# PX4FMUv2_4_6_9.net
KiCad netlist of a schematic drawn in Altium Designer
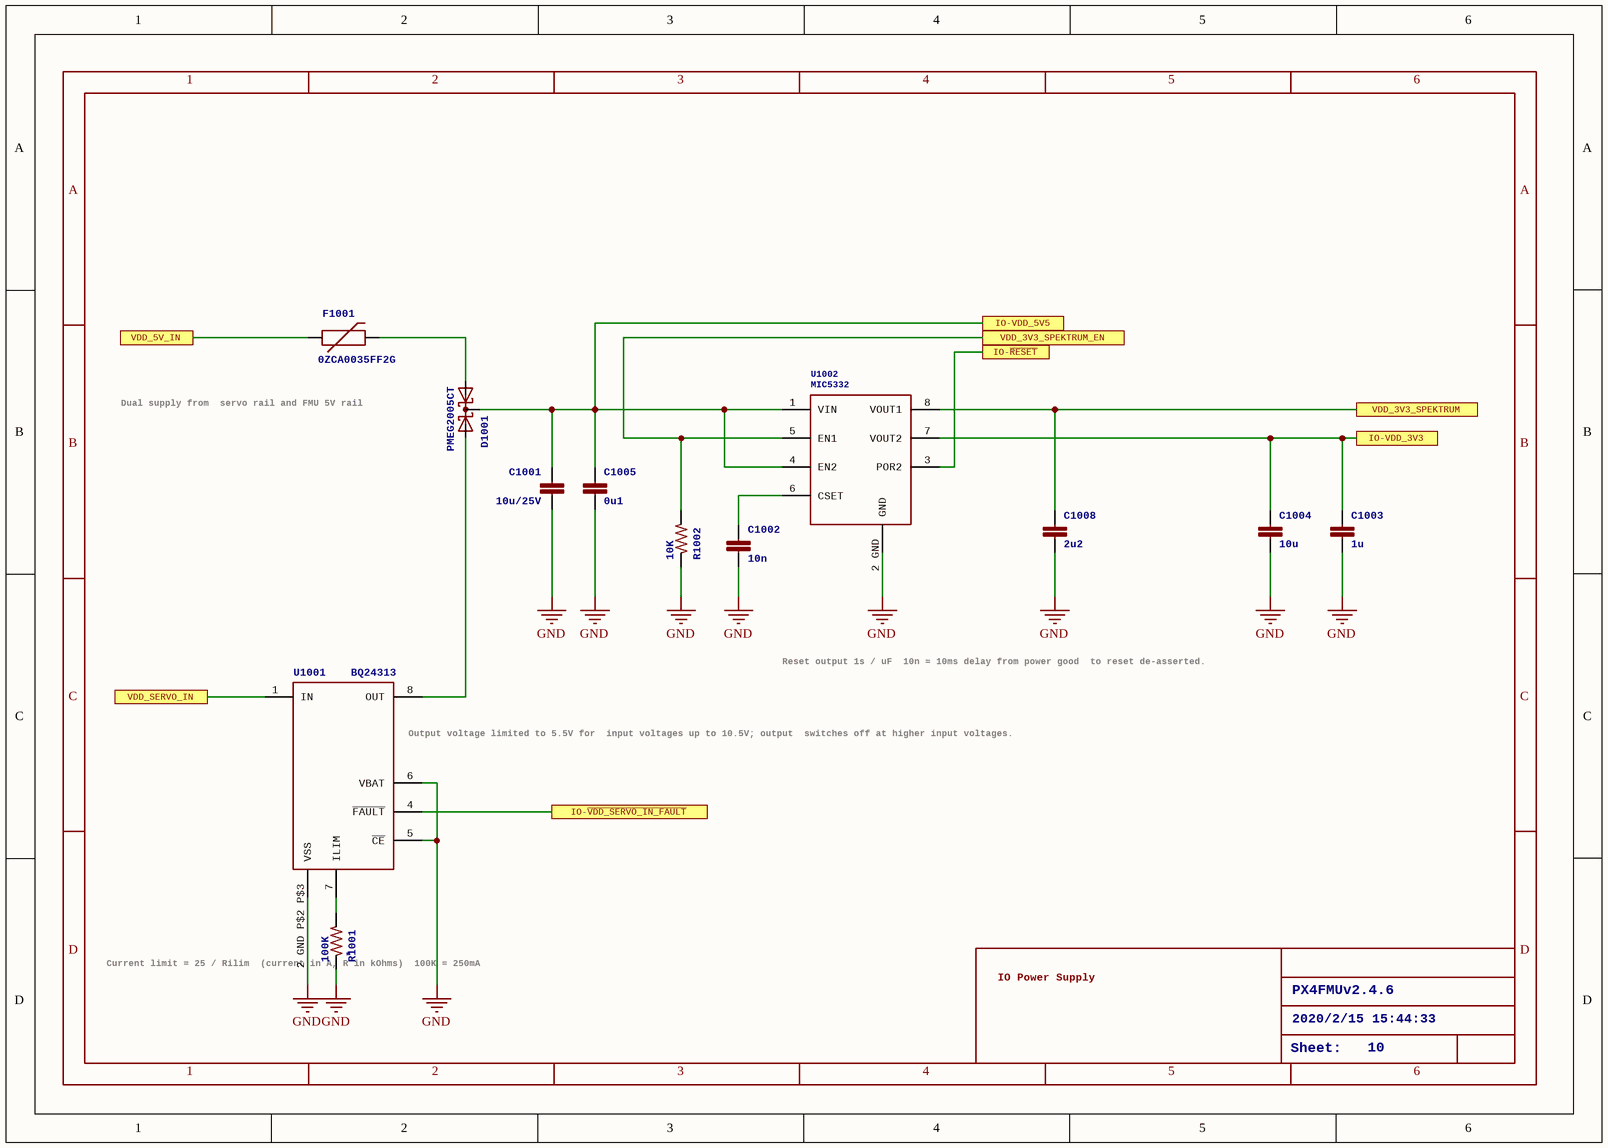
[diagram p0: PX4FMUv2.4.6_9.SchDoc]

(export (version "E")
  (design (tool "Eeschema 10.0.6"))
  (components
    (comp (ref "C1001")
      (value "10u/25V")
      (footprint "0805-CAP")
      (description "CapacitorStandard 0603 ceramic capacitor, and 0.1\" leaded capacitor.")
      (fields (field (name "PARTNO") "CL21A106KAYNNNE"))
      (libsource (lib "pixhawk2") (part "CAP0805"))
    )
    (comp (ref "C1002")
      (value "10n")
      (footprint "0402-CAP")
      (description "CapacitorStandard 0603 ceramic capacitor, and 0.1\" leaded capacitor.")
      (fields (field (name "PARTNO") "CC0402KRX7R7BB103"))
      (libsource (lib "pixhawk2") (part "CAP0402"))
    )
    (comp (ref "C1003")
      (value "1u")
      (footprint "0603-CAP")
      (description "CapacitorStandard 0603 ceramic capacitor, and 0.1\" leaded capacitor.")
      (fields (field (name "PARTNO") "CC0603ZRY5V7BB105"))
      (libsource (lib "pixhawk2") (part "CAP0603"))
    )
    (comp (ref "C1004")
      (value "10u")
      (footprint "0603-CAP")
      (description "CapacitorStandard 0603 ceramic capacitor, and 0.1\" leaded capacitor.")
      (fields (field (name "PARTNO") "C1608X5R1A106K080AC"))
      (libsource (lib "pixhawk2") (part "CAP0603"))
    )
    (comp (ref "C1005")
      (value "0u1")
      (footprint "0402-CAP")
      (description "CapacitorStandard 0603 ceramic capacitor, and 0.1\" leaded capacitor.")
      (fields (field (name "PARTNO") "CC0402ZRY5V7BB104"))
      (libsource (lib "pixhawk2") (part "CAP0402"))
    )
    (comp (ref "C1008")
      (value "2u2")
      (footprint "0402-CAP")
      (description "CapacitorStandard 0603 ceramic capacitor, and 0.1\" leaded capacitor.")
      (fields (field (name "PARTNO") "C1005X6S1C225K050BC"))
      (libsource (lib "pixhawk2") (part "CAP0402"))
    )
    (comp (ref "D1001")
      (value "PMEG2005CT")
      (footprint "SOT23-3")
      (libsource (lib "pixhawk2") (part "PMEG2005CT"))
    )
    (comp (ref "F1001")
      (value "0ZCA0035FF2G")
      (footprint "PTC-1206")
      (description "Resettable Fuse PTCResettable Fuse. Spark Fun Electronics SKU : COM-08357")
      (libsource (lib "pixhawk2") (part "PTCSMD"))
    )
    (comp (ref "R1001")
      (value "100K")
      (footprint "0402-RES")
      (fields (field (name "NAME") "*") (field (name "PARTNO") "RC0402FR-07100KL"))
      (libsource (lib "pixhawk2") (part "RESISTOR0402-RES"))
    )
    (comp (ref "R1002")
      (value "10K")
      (footprint "0402-RES")
      (fields (field (name "PARTNO") "RC0402FR-0710KL"))
      (libsource (lib "pixhawk2") (part "RESISTOR0402-RES"))
    )
    (comp (ref "U1001")
      (value "BQ24313")
      (footprint "QFN8-DSG")
      (fields (field (name "PARTNO") "BQ24313DSGT"))
      (libsource (lib "pixhawk2") (part "BQ24313"))
    )
    (comp (ref "U1002")
      (value "MIC5332")
      (footprint "MLF-8-EPAD")
      (fields (field (name "PARTNO") "MIC5332-SSYMT"))
      (libsource (lib "pixhawk2") (part "MIC5332"))
    )
  )
  (nets
    (net (code "1") (name "/IO-VDD_3V3") (class "Default")
      (node (ref "C1003") (pin "P$1") (pinfunction "1_P$1") (pintype "passive"))
      (node (ref "C1004") (pin "P$1") (pinfunction "1_P$1") (pintype "passive"))
      (node (ref "U1002") (pin "7") (pinfunction "VOUT2_7") (pintype "passive"))
    )
    (net (code "2") (name "/IO-VDD_5V5") (class "Default")
      (node (ref "C1001") (pin "P$1") (pinfunction "1_P$1") (pintype "passive"))
      (node (ref "C1005") (pin "P$1") (pinfunction "1_P$1") (pintype "passive"))
      (node (ref "D1001") (pin "3") (pinfunction "CC_3") (pintype "passive"))
      (node (ref "U1002") (pin "1") (pinfunction "VIN_1") (pintype "passive"))
      (node (ref "U1002") (pin "4") (pinfunction "EN2_4") (pintype "passive"))
    )
    (net (code "3") (name "/IO-~{RESET}") (class "Default")
      (node (ref "U1002") (pin "3") (pinfunction "POR2_3") (pintype "passive"))
    )
    (net (code "4") (name "/IO-~{VDD_SERVO_IN_FAULT}") (class "Default")
      (node (ref "U1001") (pin "4") (pinfunction "~{FAULT}_4") (pintype "passive"))
    )
    (net (code "5") (name "/VDD_3V3_SPEKTRUM") (class "Default")
      (node (ref "C1008") (pin "P$1") (pinfunction "1_P$1") (pintype "passive"))
      (node (ref "U1002") (pin "8") (pinfunction "VOUT1_8") (pintype "passive"))
    )
    (net (code "6") (name "/VDD_3V3_SPEKTRUM_EN") (class "Default")
      (node (ref "R1002") (pin "P$2") (pinfunction "2_P$2") (pintype "passive"))
      (node (ref "U1002") (pin "5") (pinfunction "EN1_5") (pintype "passive"))
    )
    (net (code "7") (name "/VDD_5V_IN") (class "Default")
      (node (ref "F1001") (pin "1") (pinfunction "1_1") (pintype "passive"))
    )
    (net (code "8") (name "/VDD_SERVO_IN") (class "Default")
      (node (ref "U1001") (pin "1") (pinfunction "IN_1") (pintype "passive"))
    )
    (net (code "9") (name "GND") (class "Default")
      (node (ref "C1001") (pin "P$2") (pinfunction "2_P$2") (pintype "passive"))
      (node (ref "C1002") (pin "P$2") (pinfunction "2_P$2") (pintype "passive"))
      (node (ref "C1003") (pin "P$2") (pinfunction "2_P$2") (pintype "passive"))
      (node (ref "C1004") (pin "P$2") (pinfunction "2_P$2") (pintype "passive"))
      (node (ref "C1005") (pin "P$2") (pinfunction "2_P$2") (pintype "passive"))
      (node (ref "C1008") (pin "P$2") (pinfunction "2_P$2") (pintype "passive"))
      (node (ref "R1001") (pin "P$1") (pinfunction "1_P$1") (pintype "passive"))
      (node (ref "R1002") (pin "P$1") (pinfunction "1_P$1") (pintype "passive"))
      (node (ref "U1001") (pin "2_GND_P$2_P$3") (pinfunction "VSS_2_GND_P$2_P$3") (pintype "passive"))
      (node (ref "U1001") (pin "5") (pinfunction "~{CE}_5") (pintype "passive"))
      (node (ref "U1001") (pin "6") (pinfunction "VBAT_6") (pintype "passive"))
      (node (ref "U1002") (pin "2_GND") (pinfunction "GND_2_GND") (pintype "passive"))
    )
    (net (code "10") (name "Net-(C1002-1)") (class "Default")
      (node (ref "C1002") (pin "P$1") (pinfunction "1_P$1") (pintype "passive"))
      (node (ref "U1002") (pin "6") (pinfunction "CSET_6") (pintype "passive"))
    )
    (net (code "11") (name "Net-(D1001-A1)") (class "Default")
      (node (ref "D1001") (pin "1") (pinfunction "A1_1") (pintype "passive"))
      (node (ref "F1001") (pin "2") (pinfunction "2_2") (pintype "passive"))
    )
    (net (code "12") (name "Net-(D1001-A2)") (class "Default")
      (node (ref "D1001") (pin "2") (pinfunction "A2_2") (pintype "passive"))
      (node (ref "U1001") (pin "8") (pinfunction "OUT_8") (pintype "passive"))
    )
    (net (code "13") (name "Net-(R1001-2)") (class "Default")
      (node (ref "R1001") (pin "P$2") (pinfunction "2_P$2") (pintype "passive"))
      (node (ref "U1001") (pin "7") (pinfunction "ILIM_7") (pintype "passive"))
    )
  )
)
